# SparkFun_Qwiic_Speaker_Amp.net
KiCad netlist of a schematic drawn in EAGLE
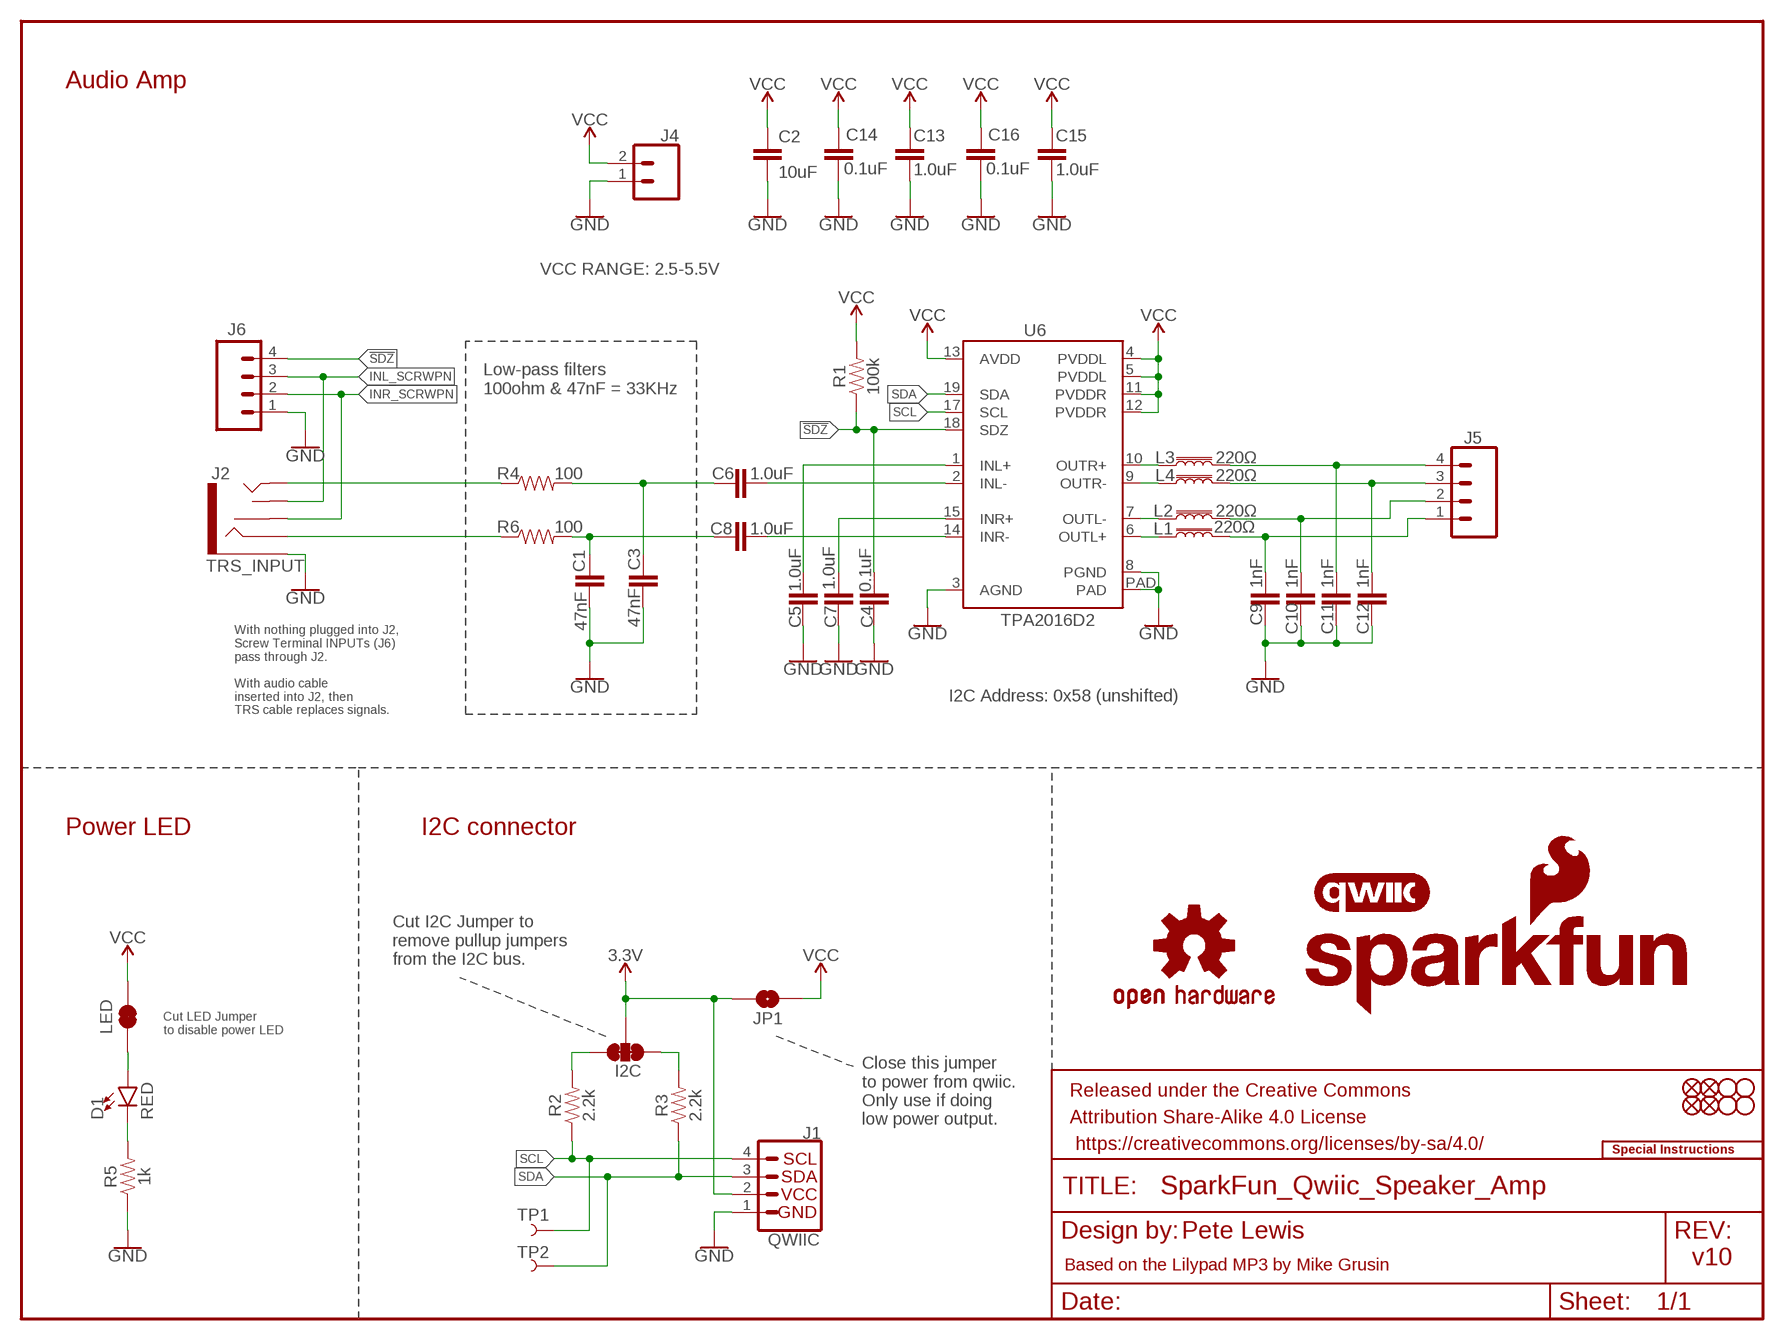
[diagram p0: schematic, sheet 1]

(export (version "E")
  (design (tool "Eeschema 10.0.6"))
  (components
    (comp (ref "C1")
      (value "47nF")
      (footprint "eagle-import:0402-TIGHT")
      (libsource (lib "eagle-import") (part "47NF-0402_TIGHT-25V-10%-X7R"))
    )
    (comp (ref "C2")
      (value "10uF")
      (footprint "eagle-import:0805")
      (libsource (lib "eagle-import") (part "10UF-0805-25V-10%"))
    )
    (comp (ref "C3")
      (value "47nF")
      (footprint "eagle-import:0402-TIGHT")
      (libsource (lib "eagle-import") (part "47NF-0402_TIGHT-25V-10%-X7R"))
    )
    (comp (ref "C4")
      (value "0.1uF")
      (footprint "eagle-import:0402-TIGHT")
      (libsource (lib "eagle-import") (part "0.1UF-0402T-16V-10%-X7R-WE"))
    )
    (comp (ref "C5")
      (value "1.0uF")
      (footprint "eagle-import:0402-TIGHT")
      (libsource (lib "eagle-import") (part "1.0UF-0402T-16V-10%"))
    )
    (comp (ref "C6")
      (value "1.0uF")
      (footprint "eagle-import:0402-TIGHT")
      (libsource (lib "eagle-import") (part "1.0UF-0402T-16V-10%"))
    )
    (comp (ref "C7")
      (value "1.0uF")
      (footprint "eagle-import:0402-TIGHT")
      (libsource (lib "eagle-import") (part "1.0UF-0402T-16V-10%"))
    )
    (comp (ref "C8")
      (value "1.0uF")
      (footprint "eagle-import:0402-TIGHT")
      (libsource (lib "eagle-import") (part "1.0UF-0402T-16V-10%"))
    )
    (comp (ref "C9")
      (value "1nF")
      (footprint "eagle-import:0402")
      (libsource (lib "eagle-import") (part "1.0NF/1000PF-0402-25V-10%-X7R"))
    )
    (comp (ref "C10")
      (value "1nF")
      (footprint "eagle-import:0402")
      (libsource (lib "eagle-import") (part "1.0NF/1000PF-0402-25V-10%-X7R"))
    )
    (comp (ref "C11")
      (value "1nF")
      (footprint "eagle-import:0402")
      (libsource (lib "eagle-import") (part "1.0NF/1000PF-0402-25V-10%-X7R"))
    )
    (comp (ref "C12")
      (value "1nF")
      (footprint "eagle-import:0402")
      (libsource (lib "eagle-import") (part "1.0NF/1000PF-0402-25V-10%-X7R"))
    )
    (comp (ref "C13")
      (value "1.0uF")
      (footprint "eagle-import:0402-TIGHT")
      (libsource (lib "eagle-import") (part "1.0UF-0402T-16V-10%"))
    )
    (comp (ref "C14")
      (value "0.1uF")
      (footprint "eagle-import:0402-TIGHT")
      (libsource (lib "eagle-import") (part "0.1UF-0402T-16V-10%-X7R-WE"))
    )
    (comp (ref "C15")
      (value "1.0uF")
      (footprint "eagle-import:0402-TIGHT")
      (libsource (lib "eagle-import") (part "1.0UF-0402T-16V-10%"))
    )
    (comp (ref "C16")
      (value "0.1uF")
      (footprint "eagle-import:0402-TIGHT")
      (libsource (lib "eagle-import") (part "0.1UF-0402T-16V-10%-X7R-WE"))
    )
    (comp (ref "D1")
      (value "RED")
      (footprint "eagle-import:LED-0603")
      (libsource (lib "eagle-import") (part "LED-RED0603"))
    )
    (comp (ref "FD1")
      (value "FIDUCIAL1X2")
      (footprint "eagle-import:FIDUCIAL-1X2")
      (libsource (lib "eagle-import") (part "FIDUCIAL1X2"))
    )
    (comp (ref "FD2")
      (value "FIDUCIAL1X2")
      (footprint "eagle-import:FIDUCIAL-1X2")
      (libsource (lib "eagle-import") (part "FIDUCIAL1X2"))
    )
    (comp (ref "FD3")
      (value "FIDUCIAL1X2")
      (footprint "eagle-import:FIDUCIAL-1X2")
      (libsource (lib "eagle-import") (part "FIDUCIAL1X2"))
    )
    (comp (ref "FD4")
      (value "FIDUCIAL1X2")
      (footprint "eagle-import:FIDUCIAL-1X2")
      (libsource (lib "eagle-import") (part "FIDUCIAL1X2"))
    )
    (comp (ref "FRAME2")
      (value "FRAME-LETTER")
      (footprint "eagle-import:CREATIVE_COMMONS")
      (libsource (lib "eagle-import") (part "FRAME-LETTER"))
    )
    (comp (ref "H1")
      (value "STAND-OFFTIGHT")
      (footprint "eagle-import:STAND-OFF-TIGHT")
      (libsource (lib "eagle-import") (part "STAND-OFFTIGHT"))
    )
    (comp (ref "H2")
      (value "STAND-OFFTIGHT")
      (footprint "eagle-import:STAND-OFF-TIGHT")
      (libsource (lib "eagle-import") (part "STAND-OFFTIGHT"))
    )
    (comp (ref "H3")
      (value "STAND-OFFTIGHT")
      (footprint "eagle-import:STAND-OFF-TIGHT")
      (libsource (lib "eagle-import") (part "STAND-OFFTIGHT"))
    )
    (comp (ref "H4")
      (value "STAND-OFFTIGHT")
      (footprint "eagle-import:STAND-OFF-TIGHT")
      (libsource (lib "eagle-import") (part "STAND-OFFTIGHT"))
    )
    (comp (ref "I2C")
      (value "JUMPER-SMT_3_2-NC_TRACE_SILK")
      (footprint "eagle-import:SMT-JUMPER_3_2-NC_TRACE_SILK")
      (libsource (lib "eagle-import") (part "JUMPER-SMT_3_2-NC_TRACE_SILK"))
    )
    (comp (ref "J1")
      (value "QWIIC")
      (footprint "eagle-import:JST04_1MM_RA")
      (libsource (lib "eagle-import") (part "QWIIC_CONNECTORJS-1MM"))
    )
    (comp (ref "J2")
      (value "TRS_INPUT")
      (footprint "eagle-import:AUDIO-JACK-3.5MM-SMD")
      (libsource (lib "eagle-import") (part "AUDIO_JACK_3.5MM_SMD"))
    )
    (comp (ref "J4")
      (value "CONN_023.5MM")
      (footprint "eagle-import:SCREWTERMINAL-3.5MM-2")
      (libsource (lib "eagle-import") (part "CONN_023.5MM"))
    )
    (comp (ref "J5")
      (value "CONN_04SCREW")
      (footprint "eagle-import:SCREWTERMINAL-3.5MM-4")
      (libsource (lib "eagle-import") (part "CONN_04SCREW"))
    )
    (comp (ref "J6")
      (value "SCREW")
      (footprint "eagle-import:SCREWTERMINAL-3.5MM-4")
      (libsource (lib "eagle-import") (part "CONN_04SCREW"))
    )
    (comp (ref "JP1")
      (value "JP1")
      (footprint "eagle-import:SMT-JUMPER_2_NO_SILK")
      (libsource (lib "eagle-import") (part "JUMPER-SMT_2_NO_SILK"))
    )
    (comp (ref "L1")
      (value "220Ω")
      (footprint "eagle-import:0805")
      (libsource (lib "eagle-import") (part "FERRITE_BEAD-0805-220Ω-100MHZ-2A"))
    )
    (comp (ref "L2")
      (value "220Ω")
      (footprint "eagle-import:0805")
      (libsource (lib "eagle-import") (part "FERRITE_BEAD-0805-220Ω-100MHZ-2A"))
    )
    (comp (ref "L3")
      (value "220Ω")
      (footprint "eagle-import:0805")
      (libsource (lib "eagle-import") (part "FERRITE_BEAD-0805-220Ω-100MHZ-2A"))
    )
    (comp (ref "L4")
      (value "220Ω")
      (footprint "eagle-import:0805")
      (libsource (lib "eagle-import") (part "FERRITE_BEAD-0805-220Ω-100MHZ-2A"))
    )
    (comp (ref "LED")
      (value "JUMPER-SMT_2_NC_TRACE_SILK")
      (footprint "eagle-import:SMT-JUMPER_2_NC_TRACE_SILK")
      (libsource (lib "eagle-import") (part "JUMPER-SMT_2_NC_TRACE_SILK"))
    )
    (comp (ref "LOGO2")
      (value "SFE_LOGO_NAME_FLAME.1_INCH")
      (footprint "eagle-import:SFE_LOGO_NAME_FLAME_.1")
      (libsource (lib "eagle-import") (part "SFE_LOGO_NAME_FLAME.1_INCH"))
    )
    (comp (ref "LOGO3")
      (value "QWIIC_LOGO_4MM")
      (footprint "eagle-import:QWIIC_4MM")
      (libsource (lib "eagle-import") (part "QWIIC_LOGO_4MM"))
    )
    (comp (ref "LOGO4")
      (value "OSHW-LOGOS")
      (footprint "eagle-import:OSHW-LOGO-S")
      (libsource (lib "eagle-import") (part "OSHW-LOGOS"))
    )
    (comp (ref "LOGO6")
      (value "SPECIAL_INSTRUCTIONS-ORDERING")
      (footprint "eagle-import:ORDERING_INSTRUCTIONS")
      (libsource (lib "eagle-import") (part "SPECIAL_INSTRUCTIONS-ORDERING"))
    )
    (comp (ref "R1")
      (value "100k")
      (footprint "eagle-import:0402-TIGHT")
      (libsource (lib "eagle-import") (part "100KOHM-0402T-1/16W-1%"))
    )
    (comp (ref "R2")
      (value "2.2k")
      (footprint "eagle-import:0402-TIGHT")
      (libsource (lib "eagle-import") (part "2.2KOHM-0402T-1/16W-1%"))
    )
    (comp (ref "R3")
      (value "2.2k")
      (footprint "eagle-import:0402-TIGHT")
      (libsource (lib "eagle-import") (part "2.2KOHM-0402T-1/16W-1%"))
    )
    (comp (ref "R4")
      (value "100")
      (footprint "eagle-import:0402-TIGHT")
      (libsource (lib "eagle-import") (part "100OHM-0402-TIGHT-1/16W-1%"))
    )
    (comp (ref "R5")
      (value "1k")
      (footprint "eagle-import:0402-TIGHT")
      (libsource (lib "eagle-import") (part "1KOHM-0402T-1/16W-1%"))
    )
    (comp (ref "R6")
      (value "100")
      (footprint "eagle-import:0402-TIGHT")
      (libsource (lib "eagle-import") (part "100OHM-0402-TIGHT-1/16W-1%"))
    )
    (comp (ref "TP1")
      (value "TEST-POINTTP_15TH_THRU")
      (footprint "eagle-import:TP_15TH")
      (libsource (lib "eagle-import") (part "TEST-POINTTP_15TH_THRU"))
    )
    (comp (ref "TP2")
      (value "TEST-POINTTP_15TH_THRU")
      (footprint "eagle-import:TP_15TH")
      (libsource (lib "eagle-import") (part "TEST-POINTTP_15TH_THRU"))
    )
    (comp (ref "U6")
      (value "TPA2016D2")
      (footprint "eagle-import:QFN-20-0.5MM")
      (libsource (lib "eagle-import") (part "TPA2016D2RTJ"))
    )
  )
  (nets
    (net (code "1") (name "/~{SDZ}") (class "Default")
      (node (ref "C4") (pin "1") (pinfunction "1_1") (pintype "passive"))
      (node (ref "J6") (pin "4") (pinfunction "4_4") (pintype "passive"))
      (node (ref "R1") (pin "1") (pinfunction "1_1") (pintype "passive"))
      (node (ref "U6") (pin "18") (pinfunction "SDZ_18") (pintype "input"))
    )
    (net (code "2") (name "3.3V") (class "Default")
      (node (ref "I2C") (pin "2") (pinfunction "2_2") (pintype "passive"))
      (node (ref "J1") (pin "2") (pinfunction "2_2") (pintype "power_in"))
      (node (ref "JP1") (pin "1") (pinfunction "1_1") (pintype "passive"))
    )
    (net (code "3") (name "GND") (class "Default")
      (node (ref "C1") (pin "2") (pinfunction "2_2") (pintype "passive"))
      (node (ref "C10") (pin "2") (pinfunction "2_2") (pintype "passive"))
      (node (ref "C11") (pin "2") (pinfunction "2_2") (pintype "passive"))
      (node (ref "C12") (pin "2") (pinfunction "2_2") (pintype "passive"))
      (node (ref "C13") (pin "2") (pinfunction "2_2") (pintype "passive"))
      (node (ref "C14") (pin "2") (pinfunction "2_2") (pintype "passive"))
      (node (ref "C15") (pin "2") (pinfunction "2_2") (pintype "passive"))
      (node (ref "C16") (pin "2") (pinfunction "2_2") (pintype "passive"))
      (node (ref "C2") (pin "2") (pinfunction "2_2") (pintype "passive"))
      (node (ref "C3") (pin "2") (pinfunction "2_2") (pintype "passive"))
      (node (ref "C4") (pin "2") (pinfunction "2_2") (pintype "passive"))
      (node (ref "C5") (pin "1") (pinfunction "1_1") (pintype "passive"))
      (node (ref "C7") (pin "1") (pinfunction "1_1") (pintype "passive"))
      (node (ref "C9") (pin "2") (pinfunction "2_2") (pintype "passive"))
      (node (ref "J1") (pin "1") (pinfunction "1_1") (pintype "power_in"))
      (node (ref "J2") (pin "SLEEVE") (pinfunction "SLEEVE_SLEEVE") (pintype "bidirectional"))
      (node (ref "J4") (pin "1") (pinfunction "1_1") (pintype "passive"))
      (node (ref "J6") (pin "1") (pinfunction "1_1") (pintype "passive"))
      (node (ref "R5") (pin "1") (pinfunction "1_1") (pintype "passive"))
      (node (ref "U6") (pin "3") (pinfunction "AGND_3") (pintype "power_in"))
      (node (ref "U6") (pin "8") (pinfunction "PGND_8") (pintype "power_in"))
      (node (ref "U6") (pin "PAD") (pinfunction "PAD_PAD") (pintype "power_in"))
    )
    (net (code "4") (name "INL_SCRWPN") (class "Default")
      (node (ref "J2") (pin "TSH") (pinfunction "TSH_TSH") (pintype "bidirectional"))
      (node (ref "J6") (pin "3") (pinfunction "3_3") (pintype "passive"))
    )
    (net (code "5") (name "INR_SCRWPN") (class "Default")
      (node (ref "J2") (pin "RSH") (pinfunction "RSH_RSH") (pintype "bidirectional"))
      (node (ref "J6") (pin "2") (pinfunction "2_2") (pintype "passive"))
    )
    (net (code "6") (name "Net-(C1-Pad1)") (class "Default")
      (node (ref "C1") (pin "1") (pinfunction "1_1") (pintype "passive"))
      (node (ref "C8") (pin "1") (pinfunction "1_1") (pintype "passive"))
      (node (ref "R6") (pin "2") (pinfunction "2_2") (pintype "passive"))
    )
    (net (code "7") (name "Net-(C3-Pad1)") (class "Default")
      (node (ref "C3") (pin "1") (pinfunction "1_1") (pintype "passive"))
      (node (ref "C6") (pin "1") (pinfunction "1_1") (pintype "passive"))
      (node (ref "R4") (pin "2") (pinfunction "2_2") (pintype "passive"))
    )
    (net (code "8") (name "Net-(C9-Pad1)") (class "Default")
      (node (ref "C9") (pin "1") (pinfunction "1_1") (pintype "passive"))
      (node (ref "J5") (pin "1") (pinfunction "1_1") (pintype "passive"))
      (node (ref "L1") (pin "2") (pinfunction "2_2") (pintype "passive"))
    )
    (net (code "9") (name "Net-(C10-Pad1)") (class "Default")
      (node (ref "C10") (pin "1") (pinfunction "1_1") (pintype "passive"))
      (node (ref "J5") (pin "2") (pinfunction "2_2") (pintype "passive"))
      (node (ref "L2") (pin "2") (pinfunction "2_2") (pintype "passive"))
    )
    (net (code "10") (name "Net-(C11-Pad1)") (class "Default")
      (node (ref "C11") (pin "1") (pinfunction "1_1") (pintype "passive"))
      (node (ref "J5") (pin "4") (pinfunction "4_4") (pintype "passive"))
      (node (ref "L3") (pin "2") (pinfunction "2_2") (pintype "passive"))
    )
    (net (code "11") (name "Net-(C12-Pad1)") (class "Default")
      (node (ref "C12") (pin "1") (pinfunction "1_1") (pintype "passive"))
      (node (ref "J5") (pin "3") (pinfunction "3_3") (pintype "passive"))
      (node (ref "L4") (pin "2") (pinfunction "2_2") (pintype "passive"))
    )
    (net (code "12") (name "Net-(D1-PadA)") (class "Default")
      (node (ref "D1") (pin "A") (pinfunction "A_A") (pintype "passive"))
      (node (ref "LED") (pin "1") (pinfunction "1_1") (pintype "passive"))
    )
    (net (code "13") (name "Net-(D1-PadC)") (class "Default")
      (node (ref "D1") (pin "C") (pinfunction "C_C") (pintype "passive"))
      (node (ref "R5") (pin "2") (pinfunction "2_2") (pintype "passive"))
    )
    (net (code "14") (name "Net-(I2C-Pad1)") (class "Default")
      (node (ref "I2C") (pin "1") (pinfunction "1_1") (pintype "passive"))
      (node (ref "R3") (pin "2") (pinfunction "2_2") (pintype "passive"))
    )
    (net (code "15") (name "Net-(I2C-Pad3)") (class "Default")
      (node (ref "I2C") (pin "3") (pinfunction "3_3") (pintype "passive"))
      (node (ref "R2") (pin "2") (pinfunction "2_2") (pintype "passive"))
    )
    (net (code "16") (name "Net-(J2-PadRING)") (class "Default")
      (node (ref "J2") (pin "RING") (pinfunction "RING_RING") (pintype "bidirectional"))
      (node (ref "R6") (pin "1") (pinfunction "1_1") (pintype "passive"))
    )
    (net (code "17") (name "Net-(J2-PadTIP)") (class "Default")
      (node (ref "J2") (pin "TIP") (pinfunction "TIP_TIP") (pintype "bidirectional"))
      (node (ref "R4") (pin "1") (pinfunction "1_1") (pintype "passive"))
    )
    (net (code "18") (name "Net-(U6-INL+)") (class "Default")
      (node (ref "C5") (pin "2") (pinfunction "2_2") (pintype "passive"))
      (node (ref "U6") (pin "1") (pinfunction "INL+_1") (pintype "input"))
    )
    (net (code "19") (name "Net-(U6-INL-)") (class "Default")
      (node (ref "C6") (pin "2") (pinfunction "2_2") (pintype "passive"))
      (node (ref "U6") (pin "2") (pinfunction "INL-_2") (pintype "input"))
    )
    (net (code "20") (name "Net-(U6-INR+)") (class "Default")
      (node (ref "C7") (pin "2") (pinfunction "2_2") (pintype "passive"))
      (node (ref "U6") (pin "15") (pinfunction "INR+_15") (pintype "input"))
    )
    (net (code "21") (name "Net-(U6-INR-)") (class "Default")
      (node (ref "C8") (pin "2") (pinfunction "2_2") (pintype "passive"))
      (node (ref "U6") (pin "14") (pinfunction "INR-_14") (pintype "input"))
    )
    (net (code "22") (name "Net-(U6-OUTL+)") (class "Default")
      (node (ref "L1") (pin "1") (pinfunction "1_1") (pintype "passive"))
      (node (ref "U6") (pin "6") (pinfunction "OUTL+_6") (pintype "output"))
    )
    (net (code "23") (name "Net-(U6-OUTL-)") (class "Default")
      (node (ref "L2") (pin "1") (pinfunction "1_1") (pintype "passive"))
      (node (ref "U6") (pin "7") (pinfunction "OUTL-_7") (pintype "output"))
    )
    (net (code "24") (name "Net-(U6-OUTR+)") (class "Default")
      (node (ref "L3") (pin "1") (pinfunction "1_1") (pintype "passive"))
      (node (ref "U6") (pin "10") (pinfunction "OUTR+_10") (pintype "output"))
    )
    (net (code "25") (name "Net-(U6-OUTR-)") (class "Default")
      (node (ref "L4") (pin "1") (pinfunction "1_1") (pintype "passive"))
      (node (ref "U6") (pin "9") (pinfunction "OUTR-_9") (pintype "output"))
    )
    (net (code "26") (name "SCL") (class "Default")
      (node (ref "J1") (pin "4") (pinfunction "4_4") (pintype "passive"))
      (node (ref "R2") (pin "1") (pinfunction "1_1") (pintype "passive"))
      (node (ref "TP1") (pin "1") (pinfunction "1_1") (pintype "bidirectional"))
      (node (ref "U6") (pin "17") (pinfunction "SCL_17") (pintype "bidirectional"))
    )
    (net (code "27") (name "SDA") (class "Default")
      (node (ref "J1") (pin "3") (pinfunction "3_3") (pintype "passive"))
      (node (ref "R3") (pin "1") (pinfunction "1_1") (pintype "passive"))
      (node (ref "TP2") (pin "1") (pinfunction "1_1") (pintype "bidirectional"))
      (node (ref "U6") (pin "19") (pinfunction "SDA_19") (pintype "bidirectional"))
    )
    (net (code "28") (name "VCC") (class "Default")
      (node (ref "C13") (pin "1") (pinfunction "1_1") (pintype "passive"))
      (node (ref "C14") (pin "1") (pinfunction "1_1") (pintype "passive"))
      (node (ref "C15") (pin "1") (pinfunction "1_1") (pintype "passive"))
      (node (ref "C16") (pin "1") (pinfunction "1_1") (pintype "passive"))
      (node (ref "C2") (pin "1") (pinfunction "1_1") (pintype "passive"))
      (node (ref "J4") (pin "2") (pinfunction "2_2") (pintype "passive"))
      (node (ref "JP1") (pin "2") (pinfunction "2_2") (pintype "passive"))
      (node (ref "LED") (pin "2") (pinfunction "2_2") (pintype "passive"))
      (node (ref "R1") (pin "2") (pinfunction "2_2") (pintype "passive"))
      (node (ref "U6") (pin "11") (pinfunction "PVDDR_11") (pintype "power_in"))
      (node (ref "U6") (pin "12") (pinfunction "PVDDR_12") (pintype "power_in"))
      (node (ref "U6") (pin "13") (pinfunction "AVDD_13") (pintype "power_in"))
      (node (ref "U6") (pin "4") (pinfunction "PVDDL_4") (pintype "power_in"))
      (node (ref "U6") (pin "5") (pinfunction "PVDDL_5") (pintype "power_in"))
    )
  )
)
